# Main.net
KiCad netlist of a schematic drawn in Altium Designer
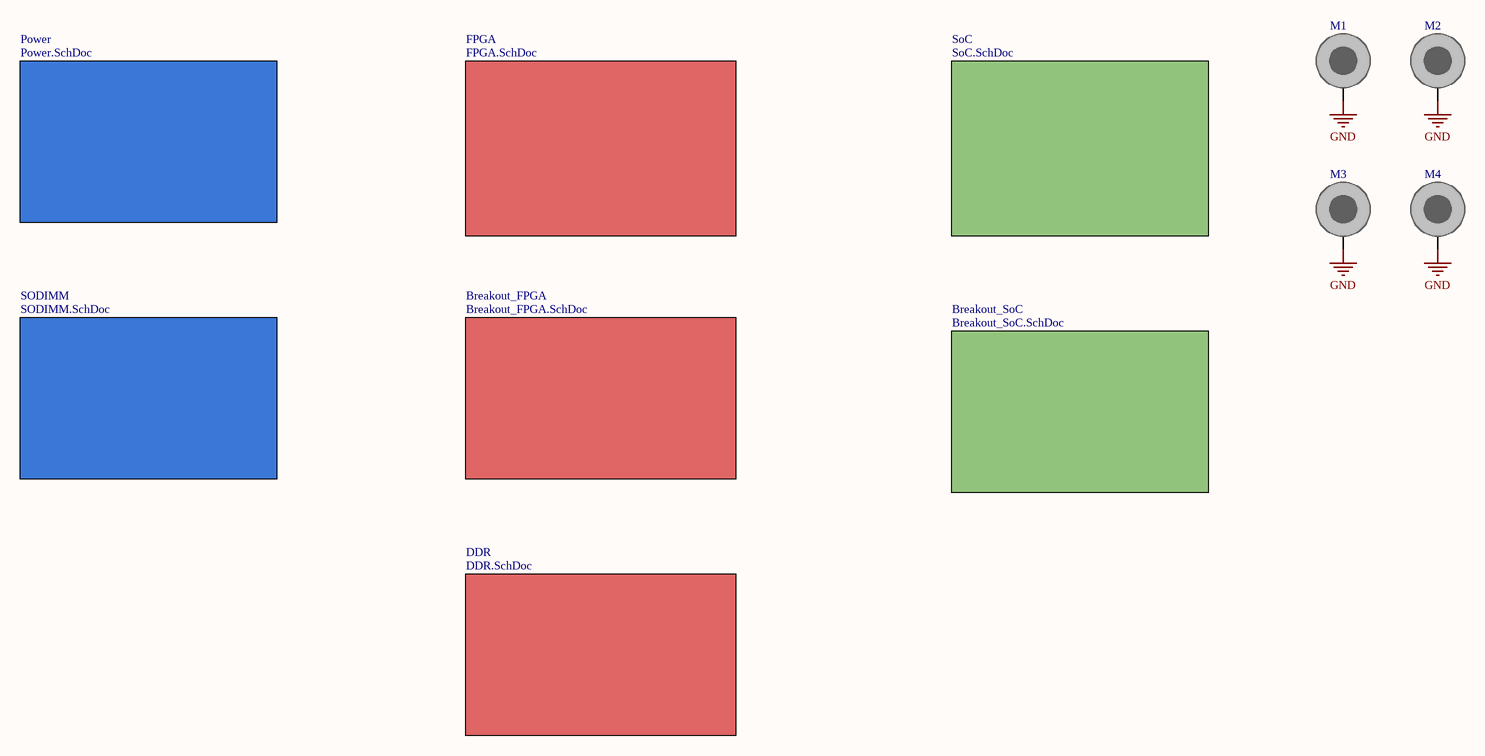
[diagram p0: Main.SchDoc]

(export (version "E")
  (design (tool "Eeschema 10.0.6"))
  (components
    (comp (ref "M1")
      (value "DNP/MH")
      (footprint "SCH_M3")
      (description "SCREW mouting, M3, 3.0mm diameter and 6.0mm PanHead")
      (libsource (lib "BWRC") (part "SCMH_M3"))
    )
    (comp (ref "M2")
      (value "DNP/MH")
      (footprint "SCH_M3")
      (description "SCREW mouting, M3, 3.0mm diameter and 6.0mm PanHead")
      (libsource (lib "BWRC") (part "SCMH_M3"))
    )
    (comp (ref "M3")
      (value "DNP/MH")
      (footprint "SCH_M3")
      (description "SCREW mouting, M3, 3.0mm diameter and 6.0mm PanHead")
      (libsource (lib "BWRC") (part "SCMH_M3"))
    )
    (comp (ref "M4")
      (value "DNP/MH")
      (footprint "SCH_M3")
      (description "SCREW mouting, M3, 3.0mm diameter and 6.0mm PanHead")
      (libsource (lib "BWRC") (part "SCMH_M3"))
    )
  )
  (nets
    (net (code "1") (name "GND") (class "Default")
      (node (ref "M1") (pin "1") (pinfunction "1_1") (pintype "passive"))
      (node (ref "M2") (pin "1") (pinfunction "1_1") (pintype "passive"))
      (node (ref "M3") (pin "1") (pinfunction "1_1") (pintype "passive"))
      (node (ref "M4") (pin "1") (pinfunction "1_1") (pintype "passive"))
    )
  )
)
